# Qwiic_Relay.net
KiCad netlist of a schematic drawn in EAGLE
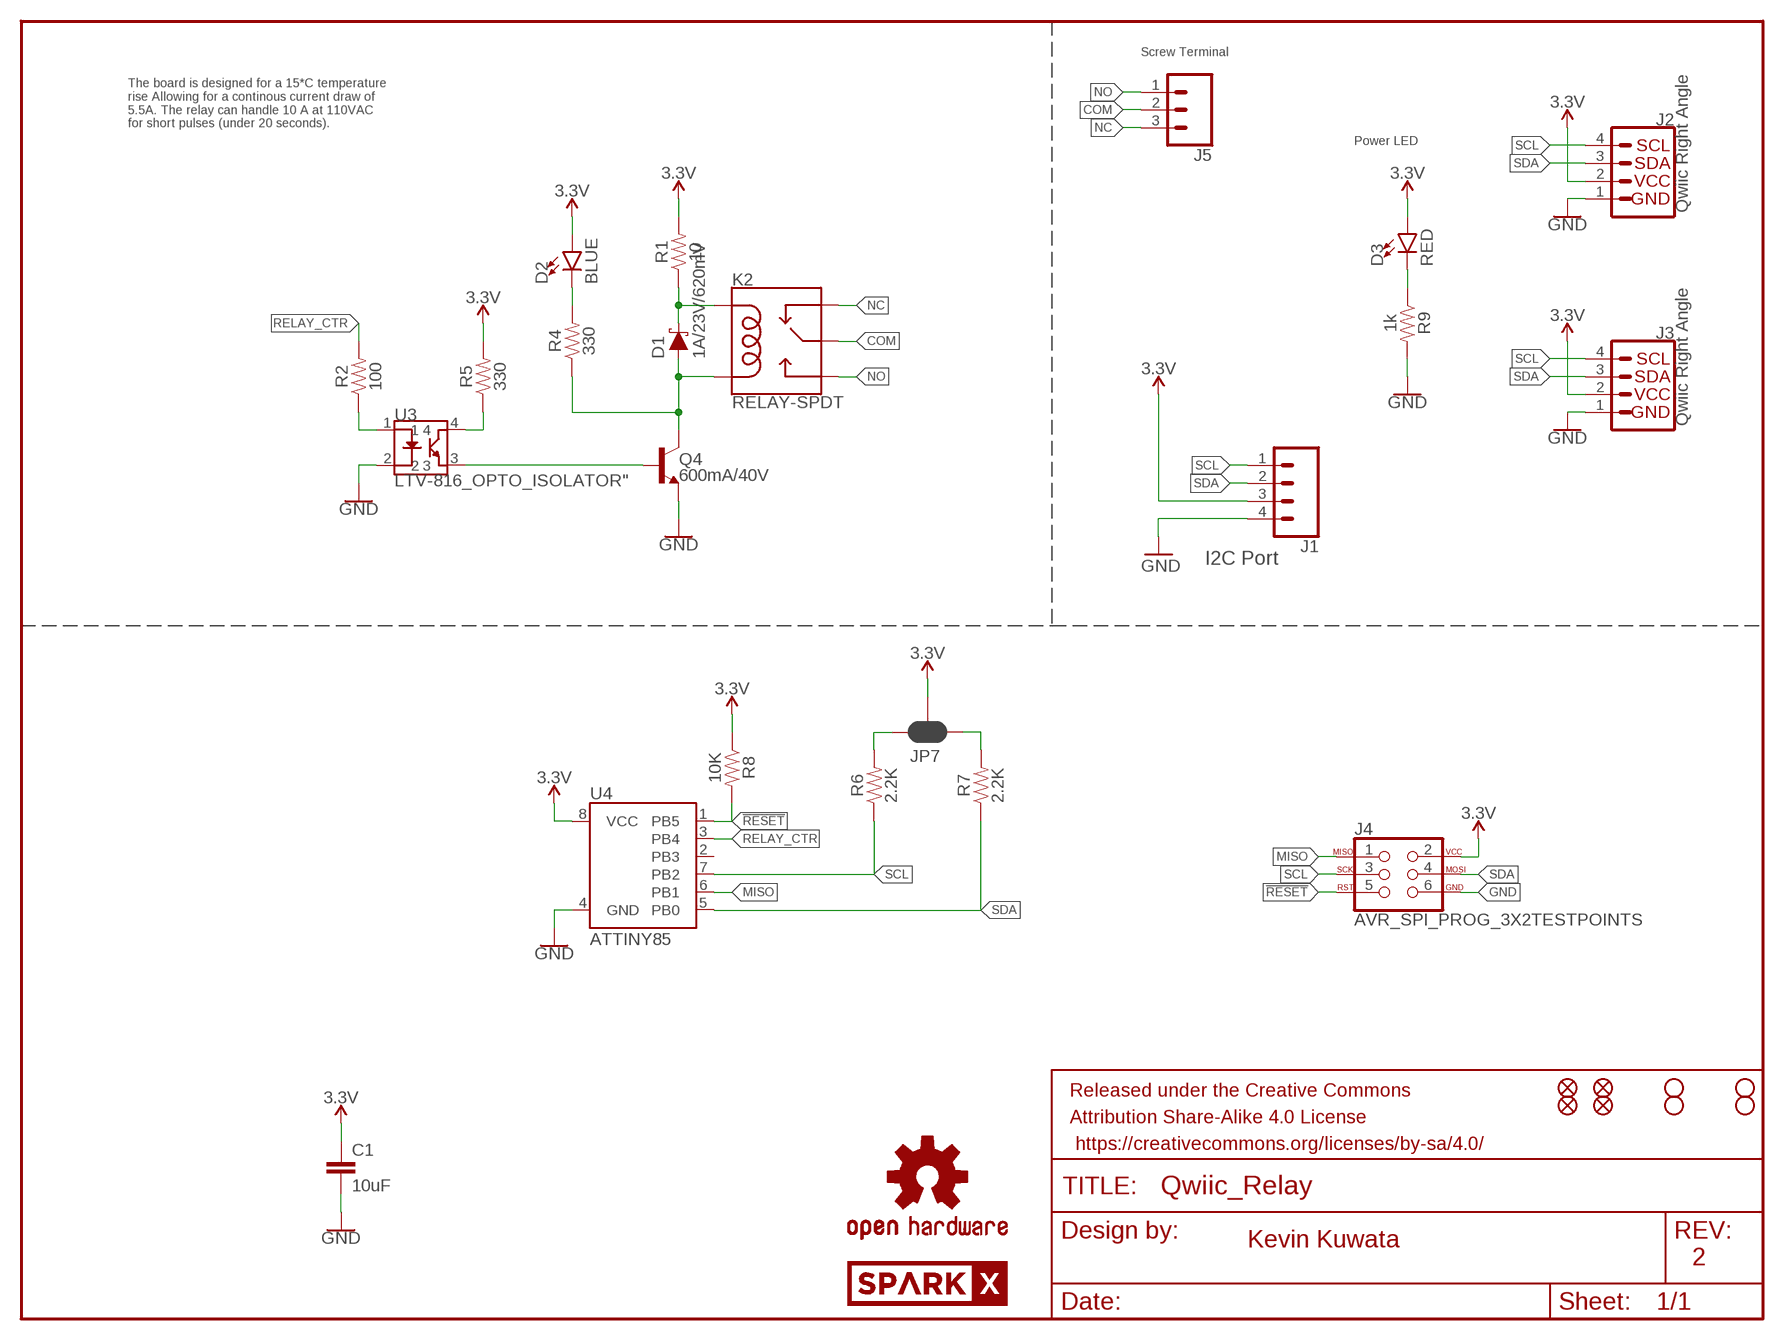
[diagram p0: schematic, sheet 1]

(export (version "E")
  (design (tool "Eeschema 10.0.6"))
  (components
    (comp (ref "C1")
      (value "10uF")
      (footprint "eagle-import:0603")
      (libsource (lib "eagle-import") (part "10UF-0603-6.3V-20%"))
    )
    (comp (ref "D1")
      (value "1A/23V/620mV")
      (footprint "eagle-import:SOD-323")
      (libsource (lib "eagle-import") (part "DIODE-SCHOTTKY-BAT20J"))
    )
    (comp (ref "D2")
      (value "BLUE")
      (footprint "eagle-import:LED-0603")
      (libsource (lib "eagle-import") (part "LED-BLUE0603"))
    )
    (comp (ref "D3")
      (value "RED")
      (footprint "eagle-import:LED-0603")
      (libsource (lib "eagle-import") (part "LED-RED0603"))
    )
    (comp (ref "FRAME1")
      (value "FRAME-LETTER")
      (footprint "eagle-import:CREATIVE_COMMONS")
      (libsource (lib "eagle-import") (part "FRAME-LETTER"))
    )
    (comp (ref "J1")
      (value "CONN_041X04_NO_SILK")
      (footprint "eagle-import:1X04_NO_SILK")
      (libsource (lib "eagle-import") (part "CONN_041X04_NO_SILK"))
    )
    (comp (ref "J2")
      (value "Qwiic Right Angle")
      (footprint "eagle-import:1X04_1MM_RA")
      (libsource (lib "eagle-import") (part "I2C_STANDARDQWIIC"))
    )
    (comp (ref "J3")
      (value "Qwiic Right Angle")
      (footprint "eagle-import:1X04_1MM_RA")
      (libsource (lib "eagle-import") (part "I2C_STANDARDQWIIC"))
    )
    (comp (ref "J4")
      (value "AVR_SPI_PROG_3X2TESTPOINTS")
      (footprint "eagle-import:2X3_TEST_POINTS")
      (libsource (lib "eagle-import") (part "AVR_SPI_PROG_3X2TESTPOINTS"))
    )
    (comp (ref "J5")
      (value "CONN_03-SCREW-5MM")
      (footprint "eagle-import:SCREWTERMINAL-5MM-3")
      (libsource (lib "eagle-import") (part "CONN_03-SCREW-5MM"))
    )
    (comp (ref "JP1")
      (value "STAND-OFF")
      (footprint "eagle-import:STAND-OFF")
      (libsource (lib "eagle-import") (part "STAND-OFF"))
    )
    (comp (ref "JP2")
      (value "FIDUCIALUFIDUCIAL")
      (footprint "eagle-import:MICRO-FIDUCIAL")
      (libsource (lib "eagle-import") (part "FIDUCIALUFIDUCIAL"))
    )
    (comp (ref "JP3")
      (value "STAND-OFF")
      (footprint "eagle-import:STAND-OFF")
      (libsource (lib "eagle-import") (part "STAND-OFF"))
    )
    (comp (ref "JP4")
      (value "STAND-OFF")
      (footprint "eagle-import:STAND-OFF")
      (libsource (lib "eagle-import") (part "STAND-OFF"))
    )
    (comp (ref "JP5")
      (value "STAND-OFF")
      (footprint "eagle-import:STAND-OFF")
      (libsource (lib "eagle-import") (part "STAND-OFF"))
    )
    (comp (ref "JP6")
      (value "FIDUCIALUFIDUCIAL")
      (footprint "eagle-import:MICRO-FIDUCIAL")
      (libsource (lib "eagle-import") (part "FIDUCIALUFIDUCIAL"))
    )
    (comp (ref "JP7")
      (value "JUMPER-SMT_3_2-NC_PASTE_SILK")
      (footprint "eagle-import:SMT-JUMPER_3_2-NC_PASTE_SILK")
      (libsource (lib "eagle-import") (part "JUMPER-SMT_3_2-NC_PASTE_SILK"))
    )
    (comp (ref "JP8")
      (value "FIDUCIALUFIDUCIAL")
      (footprint "eagle-import:MICRO-FIDUCIAL")
      (libsource (lib "eagle-import") (part "FIDUCIALUFIDUCIAL"))
    )
    (comp (ref "JP9")
      (value "FIDUCIALUFIDUCIAL")
      (footprint "eagle-import:MICRO-FIDUCIAL")
      (libsource (lib "eagle-import") (part "FIDUCIALUFIDUCIAL"))
    )
    (comp (ref "K2")
      (value "RELAY-SPDT")
      (footprint "eagle-import:RELAY_G5LE")
      (libsource (lib "eagle-import") (part "RELAY-SPDT"))
    )
    (comp (ref "LOGO1")
      (value "OSHW-LOGOMINI")
      (footprint "eagle-import:OSHW-LOGO-MINI")
      (libsource (lib "eagle-import") (part "OSHW-LOGOMINI"))
    )
    (comp (ref "Q4")
      (value "600mA/40V")
      (footprint "eagle-import:SOT23-3")
      (libsource (lib "eagle-import") (part "TRANS_NPN-MMBT2222AL"))
    )
    (comp (ref "R1")
      (value "10")
      (footprint "eagle-import:0603")
      (libsource (lib "eagle-import") (part "47KOHM-0603-1/10W-1%"))
    )
    (comp (ref "R2")
      (value "100")
      (footprint "eagle-import:0603")
      (libsource (lib "eagle-import") (part "100OHM-0603-1/4W-5%"))
    )
    (comp (ref "R4")
      (value "330")
      (footprint "eagle-import:0603")
      (libsource (lib "eagle-import") (part "300OHM-0603-1/10W-1%"))
    )
    (comp (ref "R5")
      (value "330")
      (footprint "eagle-import:0603")
      (libsource (lib "eagle-import") (part "330OHM-0603-1/10W-1%"))
    )
    (comp (ref "R6")
      (value "2.2K")
      (footprint "eagle-import:0603")
      (libsource (lib "eagle-import") (part "4.7KOHM-0603-1/10W-1%"))
    )
    (comp (ref "R7")
      (value "2.2K")
      (footprint "eagle-import:0603")
      (libsource (lib "eagle-import") (part "4.7KOHM-0603-1/10W-1%"))
    )
    (comp (ref "R8")
      (value "10K")
      (footprint "eagle-import:0603")
      (libsource (lib "eagle-import") (part "330OHM-0603-1/10W-1%"))
    )
    (comp (ref "R9")
      (value "1k")
      (footprint "eagle-import:0603")
      (libsource (lib "eagle-import") (part "330OHM-0603-1/10W-1%"))
    )
    (comp (ref "U$3")
      (value "SPARKX-LOGO4")
      (footprint "eagle-import:SPARKX-MEDIUM")
      (libsource (lib "eagle-import") (part "SPARKX-LOGO4"))
    )
    (comp (ref "U$4")
      (value "SPARKX-LOGO4")
      (footprint "eagle-import:SPARKX-MEDIUM")
      (libsource (lib "eagle-import") (part "SPARKX-LOGO4"))
    )
    (comp (ref "U3")
      (value "LTV-816_OPTO_ISOLATOR\"")
      (footprint "eagle-import:LTV-816_4PIN_DIP")
      (libsource (lib "eagle-import") (part "LTV-816_OPTO_ISOLATOR{dblquote}"))
    )
    (comp (ref "U4")
      (value "ATTINY85")
      (footprint "eagle-import:ATTINY85")
      (libsource (lib "eagle-import") (part "ATTINY85"))
    )
  )
  (nets
    (net (code "1") (name "/~{RESET}") (class "Default")
      (node (ref "J4") (pin "5") (pinfunction "5_5") (pintype "passive"))
      (node (ref "R8") (pin "2") (pinfunction "2_2") (pintype "passive"))
      (node (ref "U4") (pin "1") (pinfunction "PB5_1") (pintype "bidirectional"))
    )
    (net (code "2") (name "3.3V") (class "Default")
      (node (ref "C1") (pin "1") (pinfunction "1_1") (pintype "passive"))
      (node (ref "D2") (pin "A") (pinfunction "A_A") (pintype "passive"))
      (node (ref "D3") (pin "A") (pinfunction "A_A") (pintype "passive"))
      (node (ref "J1") (pin "3") (pinfunction "3_3") (pintype "passive"))
      (node (ref "J2") (pin "2") (pinfunction "2_2") (pintype "power_in"))
      (node (ref "J3") (pin "2") (pinfunction "2_2") (pintype "power_in"))
      (node (ref "J4") (pin "2") (pinfunction "2_2") (pintype "passive"))
      (node (ref "JP7") (pin "2") (pinfunction "2_2") (pintype "passive"))
      (node (ref "R1") (pin "2") (pinfunction "2_2") (pintype "passive"))
      (node (ref "R5") (pin "2") (pinfunction "2_2") (pintype "passive"))
      (node (ref "R8") (pin "1") (pinfunction "1_1") (pintype "passive"))
      (node (ref "U4") (pin "8") (pinfunction "VCC_8") (pintype "bidirectional"))
    )
    (net (code "3") (name "COM") (class "Default")
      (node (ref "J5") (pin "2") (pinfunction "2_2") (pintype "passive"))
      (node (ref "K2") (pin "1") (pinfunction "MAIN_1") (pintype "bidirectional"))
    )
    (net (code "4") (name "GND") (class "Default")
      (node (ref "C1") (pin "2") (pinfunction "2_2") (pintype "passive"))
      (node (ref "J1") (pin "4") (pinfunction "4_4") (pintype "passive"))
      (node (ref "J2") (pin "1") (pinfunction "1_1") (pintype "power_in"))
      (node (ref "J3") (pin "1") (pinfunction "1_1") (pintype "power_in"))
      (node (ref "J4") (pin "6") (pinfunction "6_6") (pintype "passive"))
      (node (ref "Q4") (pin "2") (pinfunction "E_2") (pintype "passive"))
      (node (ref "R9") (pin "2") (pinfunction "2_2") (pintype "passive"))
      (node (ref "U3") (pin "2") (pinfunction "2_2") (pintype "bidirectional"))
      (node (ref "U4") (pin "4") (pinfunction "GND_4") (pintype "bidirectional"))
    )
    (net (code "5") (name "MISO") (class "Default")
      (node (ref "J4") (pin "1") (pinfunction "1_1") (pintype "passive"))
      (node (ref "U4") (pin "6") (pinfunction "PB1_6") (pintype "bidirectional"))
    )
    (net (code "6") (name "NC") (class "Default")
      (node (ref "J5") (pin "3") (pinfunction "3_3") (pintype "passive"))
      (node (ref "K2") (pin "4") (pinfunction "NC_4") (pintype "bidirectional"))
    )
    (net (code "7") (name "NO") (class "Default")
      (node (ref "J5") (pin "1") (pinfunction "1_1") (pintype "passive"))
      (node (ref "K2") (pin "3") (pinfunction "NO_3") (pintype "bidirectional"))
    )
    (net (code "8") (name "Net-(D2-PadC)") (class "Default")
      (node (ref "D2") (pin "C") (pinfunction "C_C") (pintype "passive"))
      (node (ref "R4") (pin "2") (pinfunction "2_2") (pintype "passive"))
    )
    (net (code "9") (name "Net-(D3-PadC)") (class "Default")
      (node (ref "D3") (pin "C") (pinfunction "C_C") (pintype "passive"))
      (node (ref "R9") (pin "1") (pinfunction "1_1") (pintype "passive"))
    )
    (net (code "10") (name "Net-(JP7-Pad1)") (class "Default")
      (node (ref "JP7") (pin "1") (pinfunction "1_1") (pintype "passive"))
      (node (ref "R7") (pin "2") (pinfunction "2_2") (pintype "passive"))
    )
    (net (code "11") (name "Net-(JP7-Pad3)") (class "Default")
      (node (ref "JP7") (pin "3") (pinfunction "3_3") (pintype "passive"))
      (node (ref "R6") (pin "2") (pinfunction "2_2") (pintype "passive"))
    )
    (net (code "12") (name "Net-(K2-COIL1)") (class "Default")
      (node (ref "D1") (pin "C") (pinfunction "C_C") (pintype "passive"))
      (node (ref "K2") (pin "2") (pinfunction "COIL1_2") (pintype "bidirectional"))
      (node (ref "R1") (pin "1") (pinfunction "1_1") (pintype "passive"))
    )
    (net (code "13") (name "Net-(K2-COIL2)") (class "Default")
      (node (ref "D1") (pin "A") (pinfunction "A_A") (pintype "passive"))
      (node (ref "K2") (pin "5") (pinfunction "COIL2_5") (pintype "bidirectional"))
      (node (ref "Q4") (pin "3") (pinfunction "C_3") (pintype "passive"))
      (node (ref "R4") (pin "1") (pinfunction "1_1") (pintype "passive"))
    )
    (net (code "14") (name "Net-(Q4-B)") (class "Default")
      (node (ref "Q4") (pin "1") (pinfunction "B_1") (pintype "passive"))
      (node (ref "U3") (pin "3") (pinfunction "3_3") (pintype "bidirectional"))
    )
    (net (code "15") (name "Net-(R2-Pad1)") (class "Default")
      (node (ref "R2") (pin "1") (pinfunction "1_1") (pintype "passive"))
      (node (ref "U3") (pin "1") (pinfunction "1_1") (pintype "bidirectional"))
    )
    (net (code "16") (name "Net-(R5-Pad1)") (class "Default")
      (node (ref "R5") (pin "1") (pinfunction "1_1") (pintype "passive"))
      (node (ref "U3") (pin "4") (pinfunction "4_4") (pintype "bidirectional"))
    )
    (net (code "17") (name "RELAY_CTR") (class "Default")
      (node (ref "R2") (pin "2") (pinfunction "2_2") (pintype "passive"))
      (node (ref "U4") (pin "3") (pinfunction "PB4_3") (pintype "bidirectional"))
    )
    (net (code "18") (name "SCL") (class "Default")
      (node (ref "J1") (pin "1") (pinfunction "1_1") (pintype "passive"))
      (node (ref "J2") (pin "4") (pinfunction "4_4") (pintype "passive"))
      (node (ref "J3") (pin "4") (pinfunction "4_4") (pintype "passive"))
      (node (ref "J4") (pin "3") (pinfunction "3_3") (pintype "passive"))
      (node (ref "R6") (pin "1") (pinfunction "1_1") (pintype "passive"))
      (node (ref "U4") (pin "7") (pinfunction "PB2_7") (pintype "bidirectional"))
    )
    (net (code "19") (name "SDA") (class "Default")
      (node (ref "J1") (pin "2") (pinfunction "2_2") (pintype "passive"))
      (node (ref "J2") (pin "3") (pinfunction "3_3") (pintype "passive"))
      (node (ref "J3") (pin "3") (pinfunction "3_3") (pintype "passive"))
      (node (ref "J4") (pin "4") (pinfunction "4_4") (pintype "passive"))
      (node (ref "R7") (pin "1") (pinfunction "1_1") (pintype "passive"))
      (node (ref "U4") (pin "5") (pinfunction "PB0_5") (pintype "bidirectional"))
    )
    (net (code "20") (name "unconnected-(U4-PB3-Pad2)") (class "Default")
      (node (ref "U4") (pin "2") (pinfunction "PB3_2") (pintype "bidirectional"))
    )
  )
)
